# SCH_Hiking-Alarm-Trail_2024-05-05.net
KiCad netlist of a schematic drawn in EasyEDA
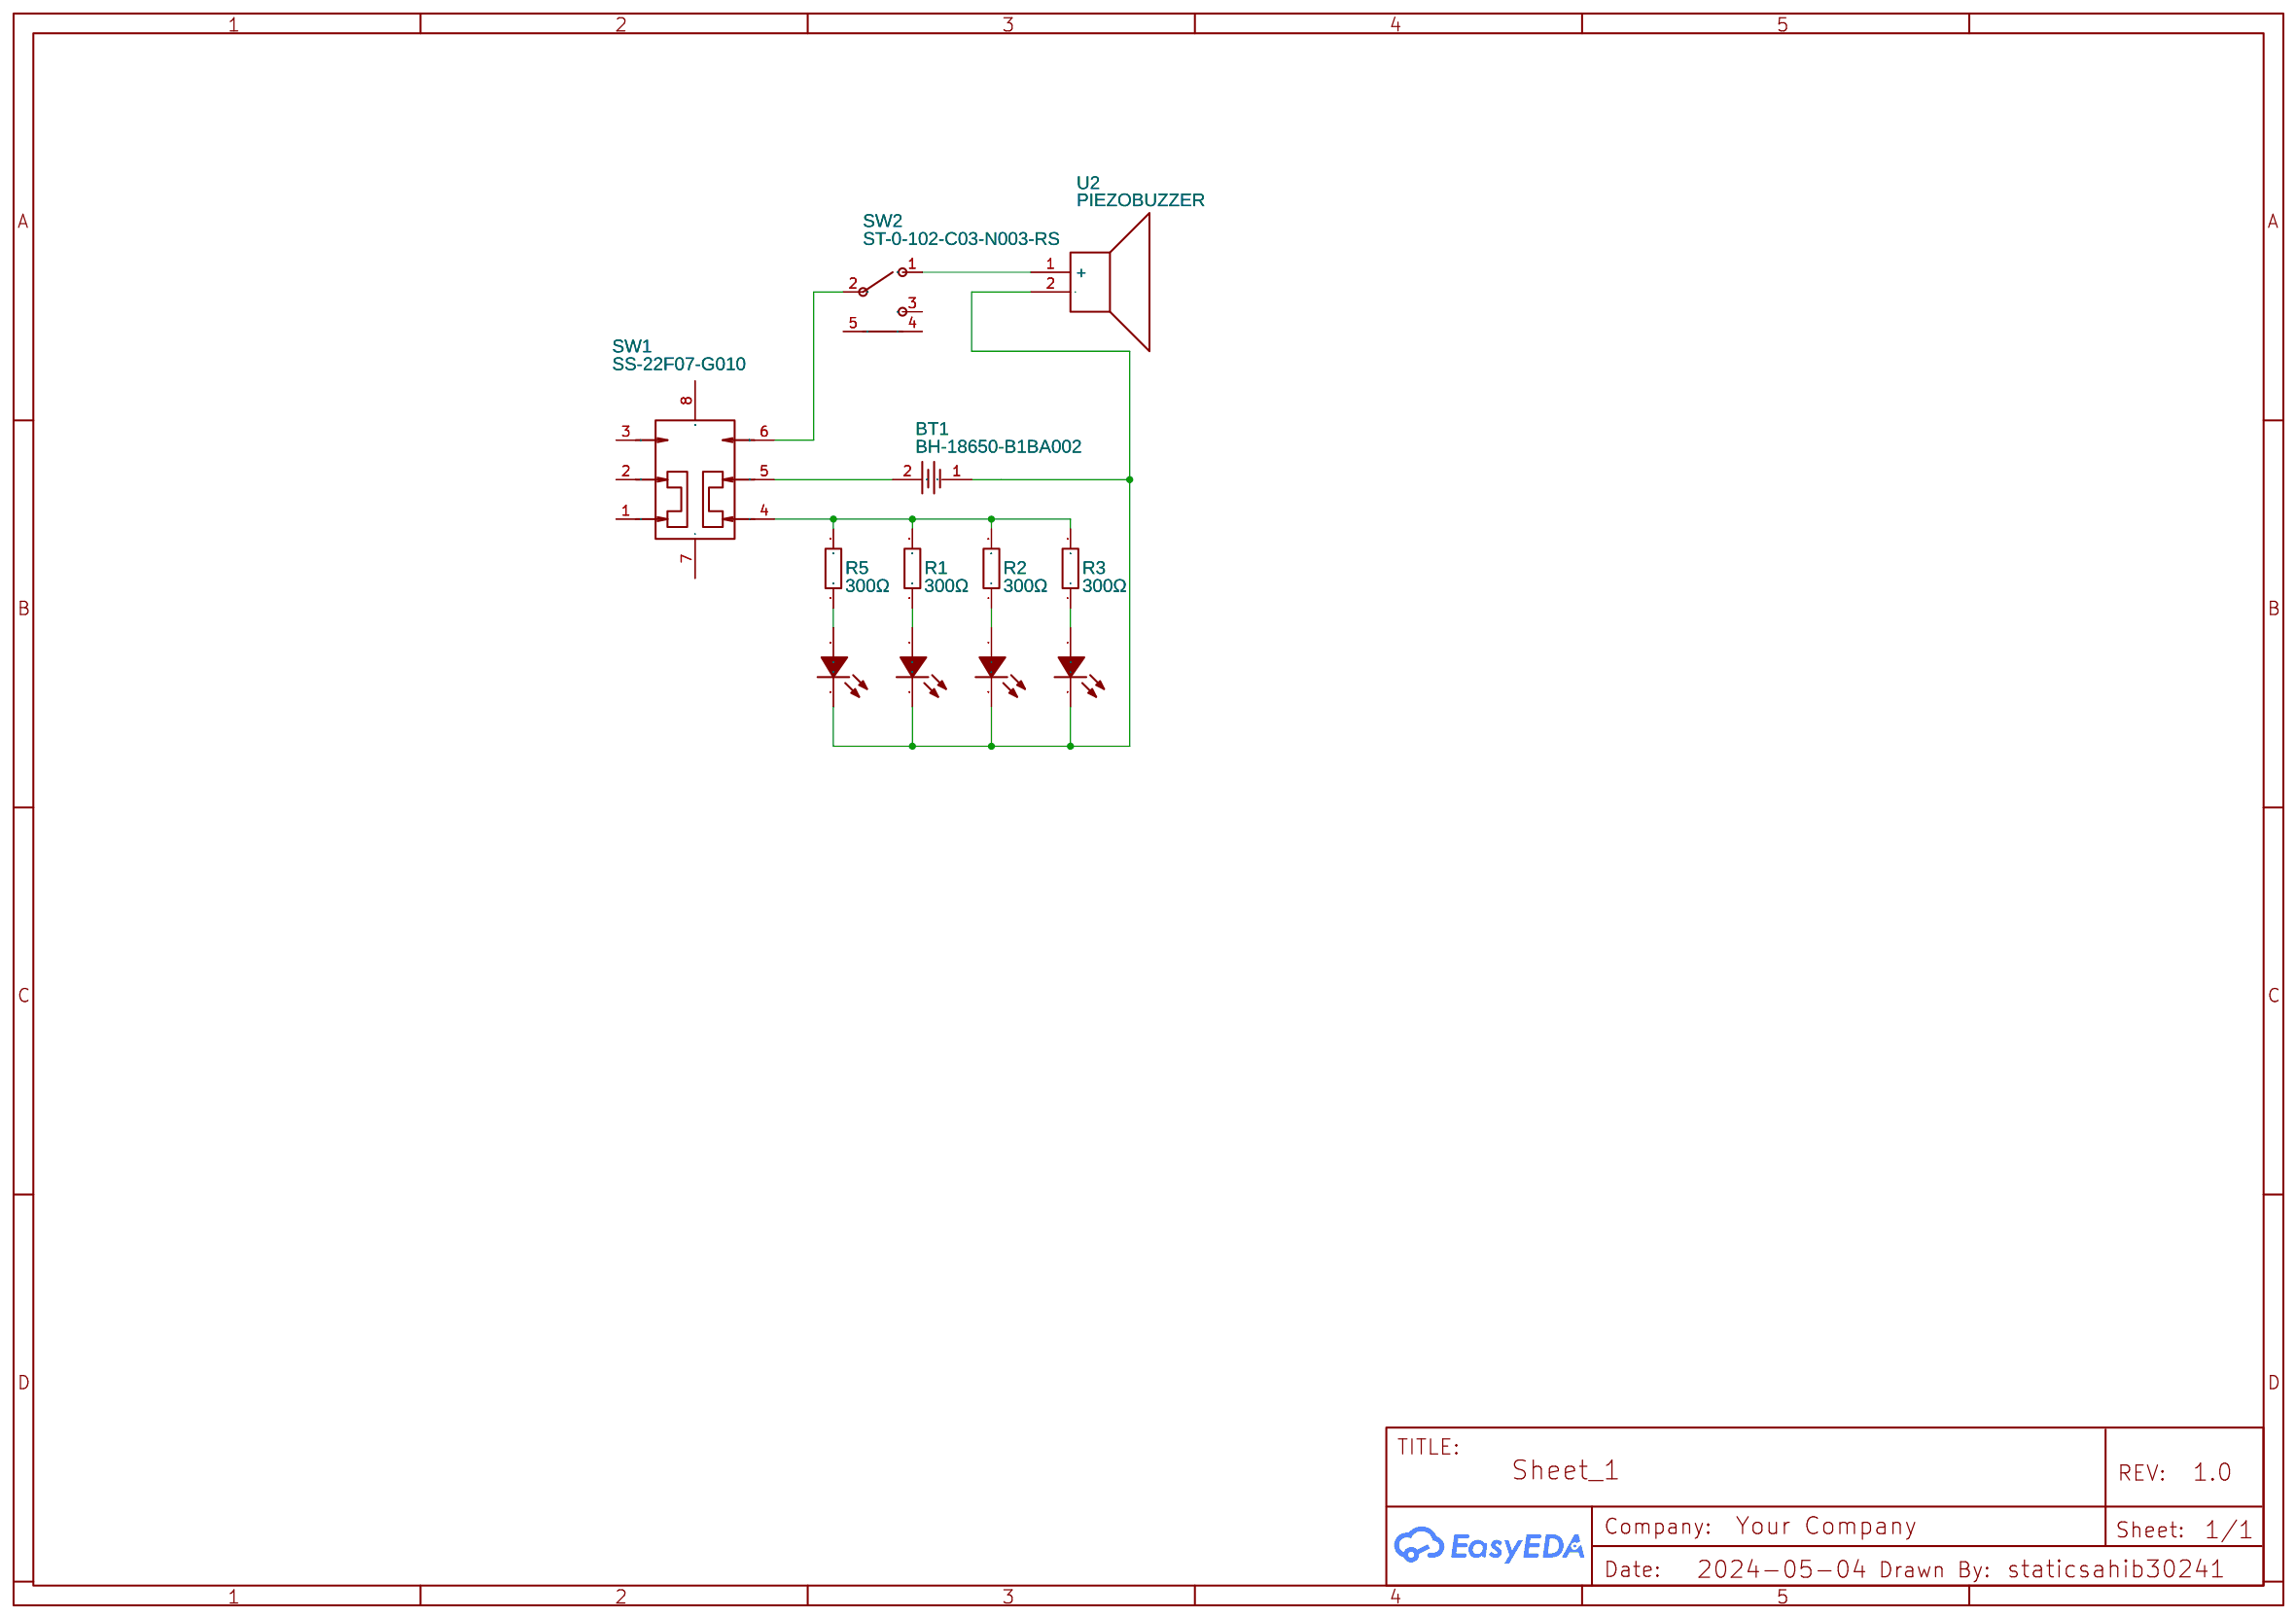
[diagram p0: schematic sheet]

(export (version "E")
  (design (tool "Eeschema 10.0.6"))
  (components
    (comp (ref "BT1")
      (value "BH-18650-B1BA002")
      (fields (field (name "Manufacturer") "MYOUNG(美阳)"))
      (libsource (lib "") (part "BH-18650-B1BA002"))
    )
    (comp (ref "LED1")
      (value "19-21SURC/S530-A5/TR8")
      (fields (field (name "Manufacturer") "EVERLIGHT(亿光)"))
      (libsource (lib "") (part "19-21SURC/S530-A5/TR8"))
    )
    (comp (ref "LED2")
      (value "19-21SURC/S530-A5/TR8")
      (fields (field (name "Manufacturer") "EVERLIGHT(亿光)"))
      (libsource (lib "") (part "19-21SURC/S530-A5/TR8"))
    )
    (comp (ref "LED3")
      (value "19-21SURC/S530-A5/TR8")
      (fields (field (name "Manufacturer") "EVERLIGHT(亿光)"))
      (libsource (lib "") (part "19-21SURC/S530-A5/TR8"))
    )
    (comp (ref "LED4")
      (value "19-21SURC/S530-A5/TR8")
      (fields (field (name "Manufacturer") "EVERLIGHT(亿光)"))
      (libsource (lib "") (part "19-21SURC/S530-A5/TR8"))
    )
    (comp (ref "R1")
      (value "300Ω")
      (fields
        (field (name "Manufacturer Part") "0805W8F3000T5E")
        (field (name "Manufacturer") "UNI-ROYAL(厚声)")
      )
      (libsource (lib "") (part "0805W8F3000T5E"))
    )
    (comp (ref "R2")
      (value "300Ω")
      (fields
        (field (name "Manufacturer Part") "0805W8F3000T5E")
        (field (name "Manufacturer") "UNI-ROYAL(厚声)")
      )
      (libsource (lib "") (part "0805W8F3000T5E"))
    )
    (comp (ref "R3")
      (value "300Ω")
      (fields
        (field (name "Manufacturer Part") "0805W8F3000T5E")
        (field (name "Manufacturer") "UNI-ROYAL(厚声)")
      )
      (libsource (lib "") (part "0805W8F3000T5E"))
    )
    (comp (ref "R5")
      (value "300Ω")
      (fields
        (field (name "Manufacturer Part") "0805W8F3000T5E")
        (field (name "Manufacturer") "UNI-ROYAL(厚声)")
      )
      (libsource (lib "") (part "0805W8F3000T5E"))
    )
    (comp (ref "SW1")
      (value "SS-22F07-G010")
      (fields (field (name "Manufacturer") "G-Switch(品赞)"))
      (libsource (lib "") (part "SS-22F07-G010"))
    )
    (comp (ref "SW2")
      (value "ST-0-102-C03-N003-RS")
      (fields (field (name "Manufacturer") "YUEN FUNG(源丰)"))
      (libsource (lib "") (part "ST-0-102-C03-N003-RS"))
    )
    (comp (ref "U2") (value "PIEZOBUZZER") (libsource (lib "") (part "PIEZOBUZZER")))
  )
  (nets
    (net (code "1") (name "Net-(BT1-Pad2)") (class "Default")
      (node (ref "BT1") (pin "2") (pinfunction "2_2") (pintype "input"))
      (node (ref "SW1") (pin "5") (pinfunction "5_5") (pintype "unspecified"))
    )
    (net (code "2") (name "Net-(LED1-A)") (class "Default")
      (node (ref "LED1") (pin "1") (pinfunction "A_1") (pintype "unspecified"))
      (node (ref "R5") (pin "1") (pinfunction "1_1") (pintype "input"))
    )
    (net (code "3") (name "Net-(LED1-C)") (class "Default")
      (node (ref "BT1") (pin "1") (pinfunction "1_1") (pintype "input"))
      (node (ref "LED1") (pin "2") (pinfunction "C_2") (pintype "unspecified"))
      (node (ref "LED2") (pin "2") (pinfunction "C_2") (pintype "unspecified"))
      (node (ref "LED3") (pin "2") (pinfunction "C_2") (pintype "unspecified"))
      (node (ref "LED4") (pin "2") (pinfunction "C_2") (pintype "unspecified"))
      (node (ref "U2") (pin "2") (pinfunction "-_2") (pintype "unspecified"))
    )
    (net (code "4") (name "Net-(LED2-A)") (class "Default")
      (node (ref "LED2") (pin "1") (pinfunction "A_1") (pintype "unspecified"))
      (node (ref "R1") (pin "1") (pinfunction "1_1") (pintype "input"))
    )
    (net (code "5") (name "Net-(LED3-A)") (class "Default")
      (node (ref "LED3") (pin "1") (pinfunction "A_1") (pintype "unspecified"))
      (node (ref "R2") (pin "1") (pinfunction "1_1") (pintype "input"))
    )
    (net (code "6") (name "Net-(LED4-A)") (class "Default")
      (node (ref "LED4") (pin "1") (pinfunction "A_1") (pintype "unspecified"))
      (node (ref "R3") (pin "1") (pinfunction "1_1") (pintype "input"))
    )
    (net (code "7") (name "Net-(R1-Pad2)") (class "Default")
      (node (ref "R1") (pin "2") (pinfunction "2_2") (pintype "input"))
      (node (ref "R2") (pin "2") (pinfunction "2_2") (pintype "input"))
      (node (ref "R3") (pin "2") (pinfunction "2_2") (pintype "input"))
      (node (ref "R5") (pin "2") (pinfunction "2_2") (pintype "input"))
      (node (ref "SW1") (pin "4") (pinfunction "4_4") (pintype "unspecified"))
    )
    (net (code "8") (name "Net-(SW1-Pad6)") (class "Default")
      (node (ref "SW1") (pin "6") (pinfunction "6_6") (pintype "unspecified"))
      (node (ref "SW2") (pin "2") (pinfunction "2_2") (pintype "input"))
    )
    (net (code "9") (name "Net-(U2-+)") (class "Default")
      (node (ref "SW2") (pin "1") (pinfunction "1_1") (pintype "input"))
      (node (ref "U2") (pin "1") (pinfunction "+_1") (pintype "unspecified"))
    )
    (net (code "10") (name "unconnected-(SW1-Pad1)") (class "Default")
      (node (ref "SW1") (pin "1") (pinfunction "1_1") (pintype "unspecified"))
    )
    (net (code "11") (name "unconnected-(SW1-Pad2)") (class "Default")
      (node (ref "SW1") (pin "2") (pinfunction "2_2") (pintype "unspecified"))
    )
    (net (code "12") (name "unconnected-(SW1-Pad3)") (class "Default")
      (node (ref "SW1") (pin "3") (pinfunction "3_3") (pintype "unspecified"))
    )
    (net (code "13") (name "unconnected-(SW1-Pad7)") (class "Default")
      (node (ref "SW1") (pin "7") (pinfunction "7_7") (pintype "unspecified"))
    )
    (net (code "14") (name "unconnected-(SW1-Pad8)") (class "Default")
      (node (ref "SW1") (pin "8") (pinfunction "8_8") (pintype "unspecified"))
    )
    (net (code "15") (name "unconnected-(SW2-Pad3)") (class "Default")
      (node (ref "SW2") (pin "3") (pinfunction "3_3") (pintype "input"))
    )
    (net (code "16") (name "unconnected-(SW2-Pad4)") (class "Default")
      (node (ref "SW2") (pin "4") (pinfunction "4_4") (pintype "unspecified"))
    )
    (net (code "17") (name "unconnected-(SW2-Pad5)") (class "Default")
      (node (ref "SW2") (pin "5") (pinfunction "5_5") (pintype "unspecified"))
    )
  )
)
